# ecgdesign.net
KiCad netlist of a schematic drawn in EAGLE
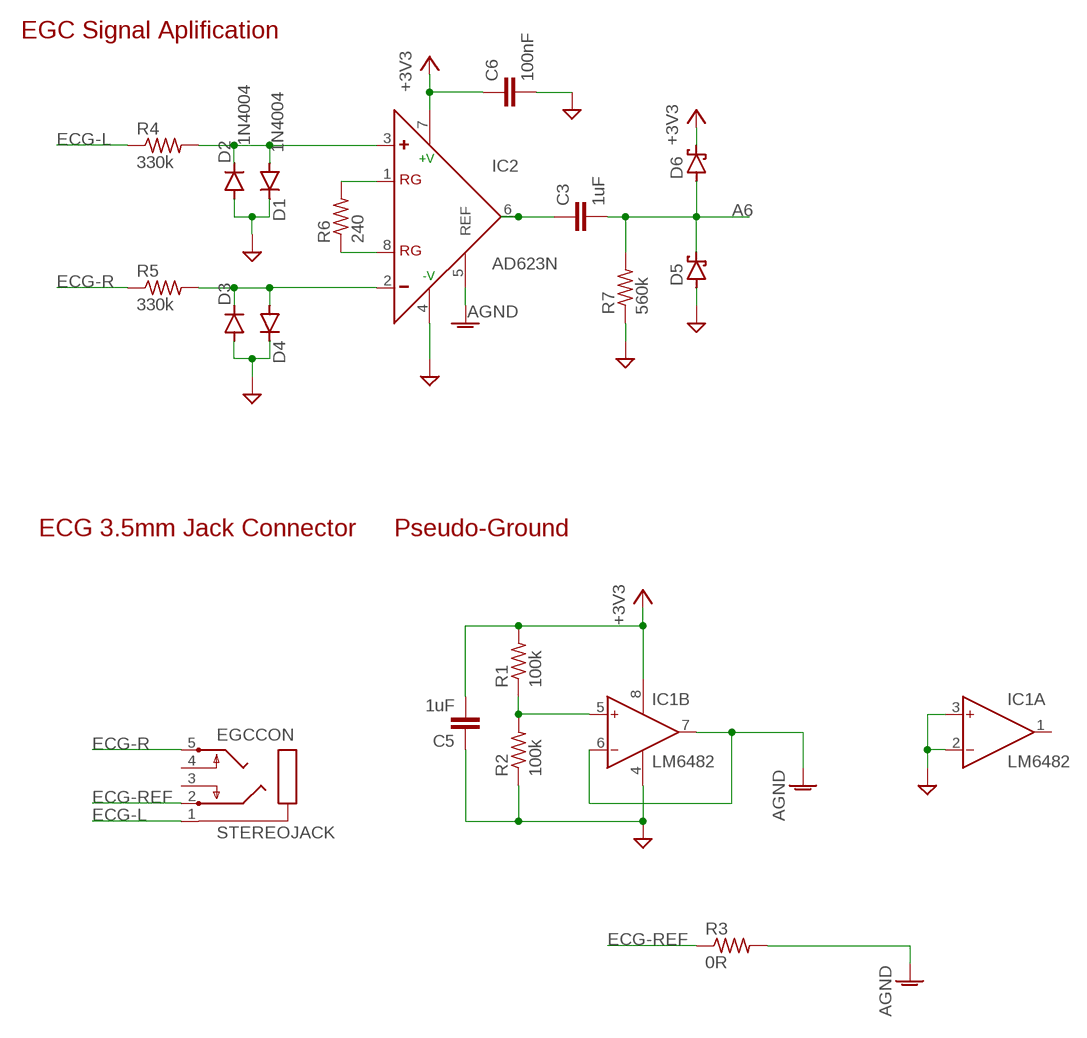
[diagram p0: schematic, sheet 1]

(export (version "E")
  (design (tool "Eeschema 10.0.6"))
  (components
    (comp (ref "C3")
      (value "1uF")
      (footprint "eagle-import:C0603")
      (libsource (lib "eagle-import") (part "C-EUC0603"))
    )
    (comp (ref "C5")
      (value "1uF")
      (footprint "eagle-import:C0603")
      (libsource (lib "eagle-import") (part "C-EUC0603"))
    )
    (comp (ref "C6")
      (value "100nF")
      (footprint "eagle-import:C0603")
      (libsource (lib "eagle-import") (part "C-EUC0603"))
    )
    (comp (ref "D1")
      (value "1N4004")
      (footprint "eagle-import:DO41-10")
      (libsource (lib "eagle-import") (part "1N4004"))
    )
    (comp (ref "D2")
      (value "1N4004")
      (footprint "eagle-import:DO41-10")
      (libsource (lib "eagle-import") (part "1N4004"))
    )
    (comp (ref "D3")
      (value "1N4004")
      (footprint "eagle-import:DO41-10")
      (libsource (lib "eagle-import") (part "1N4004"))
    )
    (comp (ref "D4")
      (value "1N4004")
      (footprint "eagle-import:DO41-10")
      (libsource (lib "eagle-import") (part "1N4004"))
    )
    (comp (ref "D5")
      (value "SCHOTTKY-DIODEDO35-7")
      (footprint "eagle-import:DO35-7")
      (libsource (lib "eagle-import") (part "SCHOTTKY-DIODEDO35-7"))
    )
    (comp (ref "D6")
      (value "SCHOTTKY-DIODEDO35-7")
      (footprint "eagle-import:DO35-7")
      (libsource (lib "eagle-import") (part "SCHOTTKY-DIODEDO35-7"))
    )
    (comp (ref "EGCCON")
      (value "STEREOJACK")
      (footprint "eagle-import:STX3100")
      (libsource (lib "eagle-import") (part "STEREOJACK"))
    )
    (comp (ref "IC1")
      (value "LM6482")
      (footprint "eagle-import:DIL08")
      (fields (field (name "MF") "ALTERA CORPORATION") (field (name "MPN") "AD826ANZ"))
      (libsource (lib "eagle-import") (part "AD826N"))
    )
    (comp (ref "IC2")
      (value "AD623N")
      (footprint "eagle-import:DIL08")
      (fields (field (name "MF") "ALTERA CORPORATION") (field (name "MPN") "AD623ANZ"))
      (libsource (lib "eagle-import") (part "AD623N"))
    )
    (comp (ref "R1")
      (value "100k")
      (footprint "eagle-import:R0603")
      (libsource (lib "eagle-import") (part "R-US_R0603"))
    )
    (comp (ref "R2")
      (value "100k")
      (footprint "eagle-import:R0603")
      (libsource (lib "eagle-import") (part "R-US_R0603"))
    )
    (comp (ref "R3")
      (value "0R")
      (footprint "eagle-import:R0603")
      (libsource (lib "eagle-import") (part "R-US_R0603"))
    )
    (comp (ref "R4")
      (value "330k")
      (footprint "eagle-import:R0603")
      (libsource (lib "eagle-import") (part "R-US_R0603"))
    )
    (comp (ref "R5")
      (value "330k")
      (footprint "eagle-import:R0603")
      (libsource (lib "eagle-import") (part "R-US_R0603"))
    )
    (comp (ref "R6")
      (value "240")
      (footprint "eagle-import:R0603")
      (libsource (lib "eagle-import") (part "R-US_R0603"))
    )
    (comp (ref "R7")
      (value "560k")
      (footprint "eagle-import:R0603")
      (libsource (lib "eagle-import") (part "R-US_R0603"))
    )
  )
  (nets
    (net (code "1") (name "+3V3") (class "Default")
      (node (ref "C5") (pin "2") (pinfunction "2_2") (pintype "passive"))
      (node (ref "C6") (pin "1") (pinfunction "1_1") (pintype "passive"))
      (node (ref "D6") (pin "C") (pinfunction "C_C") (pintype "passive"))
      (node (ref "IC1") (pin "8") (pinfunction "V+_8") (pintype "power_in"))
      (node (ref "IC2") (pin "7") (pinfunction "+V_7") (pintype "power_in"))
      (node (ref "R1") (pin "2") (pinfunction "2_2") (pintype "passive"))
    )
    (net (code "2") (name "/A6") (class "Default")
      (node (ref "C3") (pin "2") (pinfunction "2_2") (pintype "passive"))
      (node (ref "D5") (pin "C") (pinfunction "C_C") (pintype "passive"))
      (node (ref "D6") (pin "A") (pinfunction "A_A") (pintype "passive"))
      (node (ref "R7") (pin "2") (pinfunction "2_2") (pintype "passive"))
    )
    (net (code "3") (name "/ECG-L") (class "Default")
      (node (ref "EGCCON") (pin "1") (pinfunction "1_1") (pintype "passive"))
      (node (ref "R4") (pin "1") (pinfunction "1_1") (pintype "passive"))
    )
    (net (code "4") (name "/ECG-R") (class "Default")
      (node (ref "EGCCON") (pin "5") (pinfunction "5_5") (pintype "passive"))
      (node (ref "R5") (pin "1") (pinfunction "1_1") (pintype "passive"))
    )
    (net (code "5") (name "/ECG-REF") (class "Default")
      (node (ref "EGCCON") (pin "2") (pinfunction "2_2") (pintype "passive"))
      (node (ref "R3") (pin "1") (pinfunction "1_1") (pintype "passive"))
    )
    (net (code "6") (name "AGND") (class "Default")
      (node (ref "IC1") (pin "6") (pinfunction "IN-_6") (pintype "input"))
      (node (ref "IC1") (pin "7") (pinfunction "OUT_7") (pintype "output"))
      (node (ref "IC2") (pin "5") (pinfunction "REF_5") (pintype "passive"))
      (node (ref "R3") (pin "2") (pinfunction "2_2") (pintype "passive"))
    )
    (net (code "7") (name "GND") (class "Default")
      (node (ref "C5") (pin "1") (pinfunction "1_1") (pintype "passive"))
      (node (ref "C6") (pin "2") (pinfunction "2_2") (pintype "passive"))
      (node (ref "D1") (pin "C") (pinfunction "C_C") (pintype "passive"))
      (node (ref "D2") (pin "A") (pinfunction "A_A") (pintype "passive"))
      (node (ref "D3") (pin "A") (pinfunction "A_A") (pintype "passive"))
      (node (ref "D4") (pin "C") (pinfunction "C_C") (pintype "passive"))
      (node (ref "D5") (pin "A") (pinfunction "A_A") (pintype "passive"))
      (node (ref "IC1") (pin "2") (pinfunction "IN-_2") (pintype "input"))
      (node (ref "IC1") (pin "3") (pinfunction "IN+_3") (pintype "input"))
      (node (ref "IC1") (pin "4") (pinfunction "V-_4") (pintype "power_in"))
      (node (ref "IC2") (pin "4") (pinfunction "-V_4") (pintype "power_in"))
      (node (ref "R2") (pin "1") (pinfunction "1_1") (pintype "passive"))
      (node (ref "R7") (pin "1") (pinfunction "1_1") (pintype "passive"))
    )
    (net (code "8") (name "Net-(IC1B-IN+)") (class "Default")
      (node (ref "IC1") (pin "5") (pinfunction "IN+_5") (pintype "input"))
      (node (ref "R1") (pin "1") (pinfunction "1_1") (pintype "passive"))
      (node (ref "R2") (pin "2") (pinfunction "2_2") (pintype "passive"))
    )
    (net (code "9") (name "Net-(IC2-+)") (class "Default")
      (node (ref "D1") (pin "A") (pinfunction "A_A") (pintype "passive"))
      (node (ref "D2") (pin "C") (pinfunction "C_C") (pintype "passive"))
      (node (ref "IC2") (pin "3") (pinfunction "+_3") (pintype "input"))
      (node (ref "R4") (pin "2") (pinfunction "2_2") (pintype "passive"))
    )
    (net (code "10") (name "Net-(IC2--)") (class "Default")
      (node (ref "D3") (pin "C") (pinfunction "C_C") (pintype "passive"))
      (node (ref "D4") (pin "A") (pinfunction "A_A") (pintype "passive"))
      (node (ref "IC2") (pin "2") (pinfunction "-_2") (pintype "input"))
      (node (ref "R5") (pin "2") (pinfunction "2_2") (pintype "passive"))
    )
    (net (code "11") (name "Net-(IC2-OUT)") (class "Default")
      (node (ref "C3") (pin "1") (pinfunction "1_1") (pintype "passive"))
      (node (ref "IC2") (pin "6") (pinfunction "OUT_6") (pintype "output"))
    )
    (net (code "12") (name "Net-(IC2-RG-Pad1)") (class "Default")
      (node (ref "IC2") (pin "1") (pinfunction "RG_1") (pintype "passive"))
      (node (ref "R6") (pin "2") (pinfunction "2_2") (pintype "passive"))
    )
    (net (code "13") (name "Net-(IC2-RG-Pad8)") (class "Default")
      (node (ref "IC2") (pin "8") (pinfunction "RG_8") (pintype "passive"))
      (node (ref "R6") (pin "1") (pinfunction "1_1") (pintype "passive"))
    )
    (net (code "14") (name "unconnected-(EGCCON-Pad3)") (class "Default")
      (node (ref "EGCCON") (pin "3") (pinfunction "3_3") (pintype "passive"))
    )
    (net (code "15") (name "unconnected-(EGCCON-Pad4)") (class "Default")
      (node (ref "EGCCON") (pin "4") (pinfunction "4_4") (pintype "passive"))
    )
    (net (code "16") (name "unconnected-(IC1A-OUT-Pad1)") (class "Default")
      (node (ref "IC1") (pin "1") (pinfunction "OUT_1") (pintype "output"))
    )
  )
)
